# HB-UNI-Sen-TEMP-DS18B20.net
KiCad netlist of a schematic drawn in EAGLE
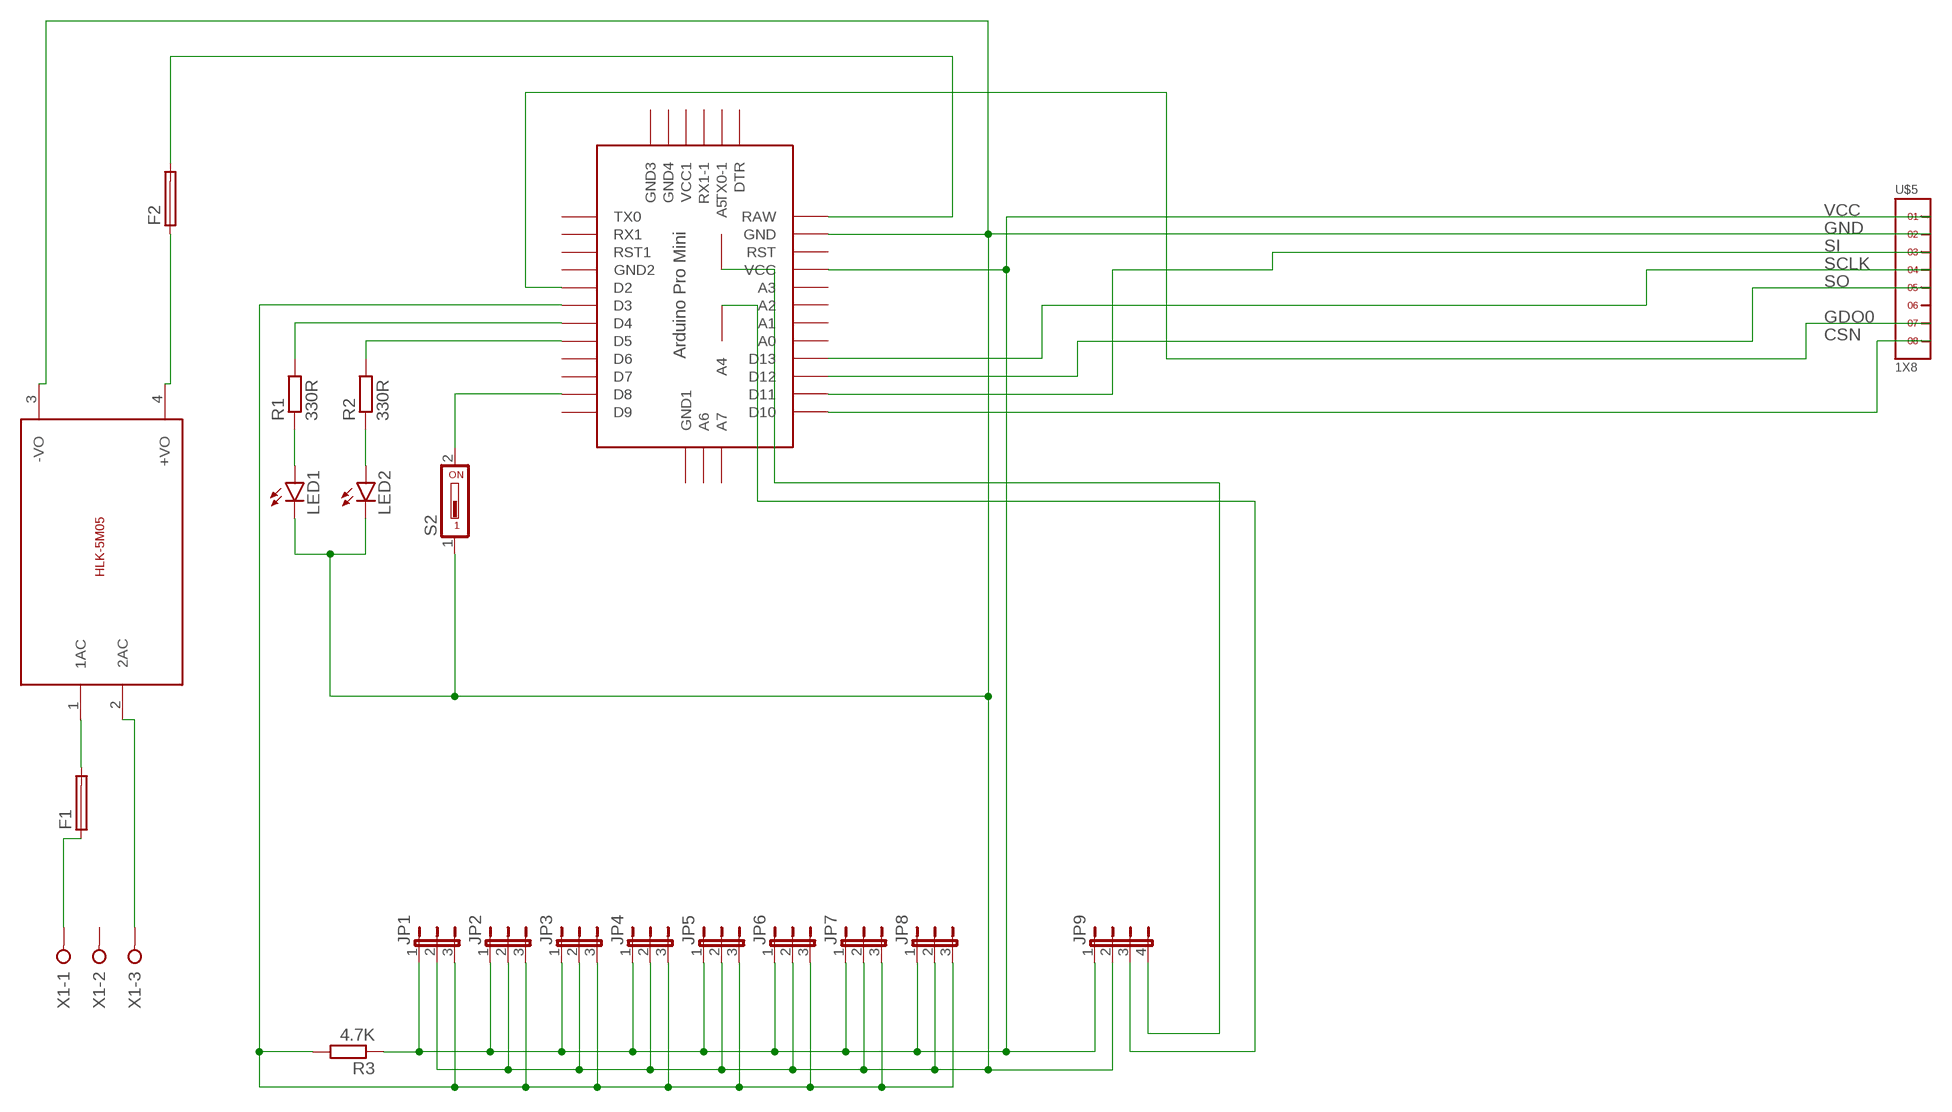
[diagram p0: schematic, sheet 1]

(export (version "E")
  (design (tool "Eeschema 10.0.6"))
  (components
    (comp (ref "F1")
      (value "GSH15")
      (footprint "eagle-import:GSH15")
      (fields (field (name "MPN") "64900001039"))
      (libsource (lib "eagle-import") (part "GSH15"))
    )
    (comp (ref "F2")
      (value "GSH15")
      (footprint "eagle-import:GSH15")
      (fields (field (name "MPN") "64900001039"))
      (libsource (lib "eagle-import") (part "GSH15"))
    )
    (comp (ref "JP1")
      (value "JP2W")
      (footprint "eagle-import:JP2W")
      (libsource (lib "eagle-import") (part "JP2W"))
    )
    (comp (ref "JP2")
      (value "JP2W")
      (footprint "eagle-import:JP2W")
      (libsource (lib "eagle-import") (part "JP2W"))
    )
    (comp (ref "JP3")
      (value "JP2W")
      (footprint "eagle-import:JP2W")
      (libsource (lib "eagle-import") (part "JP2W"))
    )
    (comp (ref "JP4")
      (value "JP2W")
      (footprint "eagle-import:JP2W")
      (libsource (lib "eagle-import") (part "JP2W"))
    )
    (comp (ref "JP5")
      (value "JP2W")
      (footprint "eagle-import:JP2W")
      (libsource (lib "eagle-import") (part "JP2W"))
    )
    (comp (ref "JP6")
      (value "JP2W")
      (footprint "eagle-import:JP2W")
      (libsource (lib "eagle-import") (part "JP2W"))
    )
    (comp (ref "JP7")
      (value "JP2W")
      (footprint "eagle-import:JP2W")
      (libsource (lib "eagle-import") (part "JP2W"))
    )
    (comp (ref "JP8")
      (value "JP2W")
      (footprint "eagle-import:JP2W")
      (libsource (lib "eagle-import") (part "JP2W"))
    )
    (comp (ref "JP9")
      (value "JP4E")
      (footprint "eagle-import:JP4")
      (libsource (lib "eagle-import") (part "JP4E"))
    )
    (comp (ref "LED1")
      (value "LED5MM")
      (footprint "eagle-import:LED5MM")
      (libsource (lib "eagle-import") (part "LED5MM"))
    )
    (comp (ref "LED2")
      (value "LED5MM")
      (footprint "eagle-import:LED5MM")
      (libsource (lib "eagle-import") (part "LED5MM"))
    )
    (comp (ref "R1")
      (value "330R")
      (footprint "eagle-import:0207_10")
      (libsource (lib "eagle-import") (part "R-EU_0207/10"))
    )
    (comp (ref "R2")
      (value "330R")
      (footprint "eagle-import:0207_10")
      (libsource (lib "eagle-import") (part "R-EU_0207/10"))
    )
    (comp (ref "R3")
      (value "4.7K")
      (footprint "eagle-import:0207_10")
      (libsource (lib "eagle-import") (part "R-EU_0207/10"))
    )
    (comp (ref "S2")
      (value "DS01")
      (footprint "eagle-import:DS-01")
      (libsource (lib "eagle-import") (part "DS01"))
    )
    (comp (ref "U$1")
      (value "ABK-PRO-MINI")
      (footprint "eagle-import:ABK-PRO-MINI")
      (libsource (lib "eagle-import") (part "ABK-PRO-MINI"))
    )
    (comp (ref "U$3")
      (value "5VDC/5W")
      (footprint "eagle-import:HLK-5M05")
      (libsource (lib "eagle-import") (part "HLK-5M05"))
    )
    (comp (ref "U$5")
      (value "1X8")
      (footprint "eagle-import:1X8")
      (libsource (lib "eagle-import") (part "1X8"))
    )
    (comp (ref "X1")
      (value "W237-3E")
      (footprint "eagle-import:W237-3E")
      (libsource (lib "eagle-import") (part "W237-3E"))
    )
  )
  (nets
    (net (code "1") (name "/CSN") (class "Default")
      (node (ref "U$1") (pin "D10") (pinfunction "D10_D10") (pintype "bidirectional"))
      (node (ref "U$5") (pin "8") (pinfunction "8_8") (pintype "bidirectional"))
    )
    (net (code "2") (name "/GDO0") (class "Default")
      (node (ref "U$1") (pin "D2") (pinfunction "D2_D2") (pintype "bidirectional"))
      (node (ref "U$5") (pin "7") (pinfunction "7_7") (pintype "bidirectional"))
    )
    (net (code "3") (name "/GND") (class "Default")
      (node (ref "JP1") (pin "2") (pinfunction "2_2") (pintype "passive"))
      (node (ref "JP2") (pin "2") (pinfunction "2_2") (pintype "passive"))
      (node (ref "JP3") (pin "2") (pinfunction "2_2") (pintype "passive"))
      (node (ref "JP4") (pin "2") (pinfunction "2_2") (pintype "passive"))
      (node (ref "JP5") (pin "2") (pinfunction "2_2") (pintype "passive"))
      (node (ref "JP6") (pin "2") (pinfunction "2_2") (pintype "passive"))
      (node (ref "JP7") (pin "2") (pinfunction "2_2") (pintype "passive"))
      (node (ref "JP8") (pin "2") (pinfunction "2_2") (pintype "passive"))
      (node (ref "JP9") (pin "2") (pinfunction "2_2") (pintype "passive"))
      (node (ref "LED1") (pin "K") (pinfunction "C_K") (pintype "passive"))
      (node (ref "LED2") (pin "K") (pinfunction "C_K") (pintype "passive"))
      (node (ref "S2") (pin "1") (pinfunction "1_1") (pintype "passive"))
      (node (ref "U$1") (pin "GND") (pinfunction "GND_GND") (pintype "bidirectional"))
      (node (ref "U$3") (pin "3") (pinfunction "-VO_3") (pintype "bidirectional"))
      (node (ref "U$5") (pin "2") (pinfunction "2_2") (pintype "bidirectional"))
    )
    (net (code "4") (name "/SCLK") (class "Default")
      (node (ref "U$1") (pin "D13") (pinfunction "D13_D13") (pintype "bidirectional"))
      (node (ref "U$5") (pin "4") (pinfunction "4_4") (pintype "bidirectional"))
    )
    (net (code "5") (name "/SI") (class "Default")
      (node (ref "U$1") (pin "D11") (pinfunction "D11_D11") (pintype "bidirectional"))
      (node (ref "U$5") (pin "3") (pinfunction "3_3") (pintype "bidirectional"))
    )
    (net (code "6") (name "/SO") (class "Default")
      (node (ref "U$1") (pin "D12") (pinfunction "D12_D12") (pintype "bidirectional"))
      (node (ref "U$5") (pin "5") (pinfunction "5_5") (pintype "bidirectional"))
    )
    (net (code "7") (name "/VCC") (class "Default")
      (node (ref "JP1") (pin "1") (pinfunction "1_1") (pintype "passive"))
      (node (ref "JP2") (pin "1") (pinfunction "1_1") (pintype "passive"))
      (node (ref "JP3") (pin "1") (pinfunction "1_1") (pintype "passive"))
      (node (ref "JP4") (pin "1") (pinfunction "1_1") (pintype "passive"))
      (node (ref "JP5") (pin "1") (pinfunction "1_1") (pintype "passive"))
      (node (ref "JP6") (pin "1") (pinfunction "1_1") (pintype "passive"))
      (node (ref "JP7") (pin "1") (pinfunction "1_1") (pintype "passive"))
      (node (ref "JP8") (pin "1") (pinfunction "1_1") (pintype "passive"))
      (node (ref "JP9") (pin "1") (pinfunction "1_1") (pintype "passive"))
      (node (ref "R3") (pin "1") (pinfunction "1_1") (pintype "passive"))
      (node (ref "U$1") (pin "VCC") (pinfunction "VCC_VCC") (pintype "bidirectional"))
      (node (ref "U$5") (pin "1") (pinfunction "1_1") (pintype "bidirectional"))
    )
    (net (code "8") (name "Net-(F2-Pad2)") (class "Default")
      (node (ref "F2") (pin "2") (pinfunction "2_2") (pintype "passive"))
      (node (ref "U$1") (pin "RAW") (pinfunction "RAW_RAW") (pintype "bidirectional"))
    )
    (net (code "9") (name "Net-(JP1-Pad3)") (class "Default")
      (node (ref "JP1") (pin "3") (pinfunction "3_3") (pintype "passive"))
      (node (ref "JP2") (pin "3") (pinfunction "3_3") (pintype "passive"))
      (node (ref "JP3") (pin "3") (pinfunction "3_3") (pintype "passive"))
      (node (ref "JP4") (pin "3") (pinfunction "3_3") (pintype "passive"))
      (node (ref "JP5") (pin "3") (pinfunction "3_3") (pintype "passive"))
      (node (ref "JP6") (pin "3") (pinfunction "3_3") (pintype "passive"))
      (node (ref "JP7") (pin "3") (pinfunction "3_3") (pintype "passive"))
      (node (ref "JP8") (pin "3") (pinfunction "3_3") (pintype "passive"))
      (node (ref "R3") (pin "2") (pinfunction "2_2") (pintype "passive"))
      (node (ref "U$1") (pin "D3") (pinfunction "D3_D3") (pintype "bidirectional"))
    )
    (net (code "10") (name "Net-(JP9-Pad3)") (class "Default")
      (node (ref "JP9") (pin "3") (pinfunction "3_3") (pintype "passive"))
      (node (ref "U$1") (pin "A4") (pinfunction "A4_A4") (pintype "bidirectional"))
    )
    (net (code "11") (name "Net-(JP9-Pad4)") (class "Default")
      (node (ref "JP9") (pin "4") (pinfunction "4_4") (pintype "passive"))
      (node (ref "U$1") (pin "A5") (pinfunction "A5_A5") (pintype "bidirectional"))
    )
    (net (code "12") (name "Net-(LED1-PadA)") (class "Default")
      (node (ref "LED1") (pin "A") (pinfunction "A_A") (pintype "passive"))
      (node (ref "R1") (pin "1") (pinfunction "1_1") (pintype "passive"))
    )
    (net (code "13") (name "Net-(LED2-PadA)") (class "Default")
      (node (ref "LED2") (pin "A") (pinfunction "A_A") (pintype "passive"))
      (node (ref "R2") (pin "1") (pinfunction "1_1") (pintype "passive"))
    )
    (net (code "14") (name "Net-(R1-Pad2)") (class "Default")
      (node (ref "R1") (pin "2") (pinfunction "2_2") (pintype "passive"))
      (node (ref "U$1") (pin "D4") (pinfunction "D4_D4") (pintype "bidirectional"))
    )
    (net (code "15") (name "Net-(R2-Pad2)") (class "Default")
      (node (ref "R2") (pin "2") (pinfunction "2_2") (pintype "passive"))
      (node (ref "U$1") (pin "D5") (pinfunction "D5_D5") (pintype "bidirectional"))
    )
    (net (code "16") (name "Net-(S2-Pad2)") (class "Default")
      (node (ref "S2") (pin "2") (pinfunction "2_2") (pintype "passive"))
      (node (ref "U$1") (pin "D8") (pinfunction "D8_D8") (pintype "bidirectional"))
    )
    (net (code "17") (name "Net-(U$3-+VO)") (class "Default")
      (node (ref "F2") (pin "1") (pinfunction "1_1") (pintype "passive"))
      (node (ref "U$3") (pin "4") (pinfunction "+VO_4") (pintype "bidirectional"))
    )
    (net (code "18") (name "Net-(U$3-1AC)") (class "Default")
      (node (ref "F1") (pin "2") (pinfunction "2_2") (pintype "passive"))
      (node (ref "U$3") (pin "1") (pinfunction "1AC_1") (pintype "bidirectional"))
    )
    (net (code "19") (name "Net-(U$3-2AC)") (class "Default")
      (node (ref "U$3") (pin "2") (pinfunction "2AC_2") (pintype "bidirectional"))
      (node (ref "X1") (pin "3") (pinfunction "KL_3") (pintype "passive"))
    )
    (net (code "20") (name "Net-(X1A-KL)") (class "Default")
      (node (ref "F1") (pin "1") (pinfunction "1_1") (pintype "passive"))
      (node (ref "X1") (pin "1") (pinfunction "KL_1") (pintype "passive"))
    )
    (net (code "21") (name "unconnected-(U$1-GND1-PadGND4)") (class "Default")
      (node (ref "U$1") (pin "GND4") (pinfunction "GND1_GND4") (pintype "bidirectional"))
    )
    (net (code "22") (name "unconnected-(U$1-GND2-PadGND1)") (class "Default")
      (node (ref "U$1") (pin "GND1") (pinfunction "GND2_GND1") (pintype "bidirectional"))
    )
    (net (code "23") (name "unconnected-(U$1-GND3-PadGND2)") (class "Default")
      (node (ref "U$1") (pin "GND2") (pinfunction "GND3_GND2") (pintype "bidirectional"))
    )
    (net (code "24") (name "unconnected-(U$1-GND4-PadGND3)") (class "Default")
      (node (ref "U$1") (pin "GND3") (pinfunction "GND4_GND3") (pintype "bidirectional"))
    )
    (net (code "25") (name "unconnected-(U$1-PadA0)") (class "Default")
      (node (ref "U$1") (pin "A0") (pinfunction "A0_A0") (pintype "bidirectional"))
    )
    (net (code "26") (name "unconnected-(U$1-PadA1)") (class "Default")
      (node (ref "U$1") (pin "A1") (pinfunction "A1_A1") (pintype "bidirectional"))
    )
    (net (code "27") (name "unconnected-(U$1-PadA2)") (class "Default")
      (node (ref "U$1") (pin "A2") (pinfunction "A2_A2") (pintype "bidirectional"))
    )
    (net (code "28") (name "unconnected-(U$1-PadA3)") (class "Default")
      (node (ref "U$1") (pin "A3") (pinfunction "A3_A3") (pintype "bidirectional"))
    )
    (net (code "29") (name "unconnected-(U$1-PadA6)") (class "Default")
      (node (ref "U$1") (pin "A6") (pinfunction "A6_A6") (pintype "bidirectional"))
    )
    (net (code "30") (name "unconnected-(U$1-PadA7)") (class "Default")
      (node (ref "U$1") (pin "A7") (pinfunction "A7_A7") (pintype "bidirectional"))
    )
    (net (code "31") (name "unconnected-(U$1-PadD6)") (class "Default")
      (node (ref "U$1") (pin "D6") (pinfunction "D6_D6") (pintype "bidirectional"))
    )
    (net (code "32") (name "unconnected-(U$1-PadD7)") (class "Default")
      (node (ref "U$1") (pin "D7") (pinfunction "D7_D7") (pintype "bidirectional"))
    )
    (net (code "33") (name "unconnected-(U$1-PadD9)") (class "Default")
      (node (ref "U$1") (pin "D9") (pinfunction "D9_D9") (pintype "bidirectional"))
    )
    (net (code "34") (name "unconnected-(U$1-PadDTR)") (class "Default")
      (node (ref "U$1") (pin "DTR") (pinfunction "DTR_DTR") (pintype "bidirectional"))
    )
    (net (code "35") (name "unconnected-(U$1-PadRST)") (class "Default")
      (node (ref "U$1") (pin "RST") (pinfunction "RST_RST") (pintype "bidirectional"))
    )
    (net (code "36") (name "unconnected-(U$1-PadRST1)") (class "Default")
      (node (ref "U$1") (pin "RST1") (pinfunction "RST1_RST1") (pintype "bidirectional"))
    )
    (net (code "37") (name "unconnected-(U$1-PadRX1)") (class "Default")
      (node (ref "U$1") (pin "RX1") (pinfunction "RX1_RX1") (pintype "bidirectional"))
    )
    (net (code "38") (name "unconnected-(U$1-PadRX1-1)") (class "Default")
      (node (ref "U$1") (pin "RX1-1") (pinfunction "RX1-1_RX1-1") (pintype "bidirectional"))
    )
    (net (code "39") (name "unconnected-(U$1-PadTX0)") (class "Default")
      (node (ref "U$1") (pin "TX0") (pinfunction "TX0_TX0") (pintype "bidirectional"))
    )
    (net (code "40") (name "unconnected-(U$1-PadTX0-1)") (class "Default")
      (node (ref "U$1") (pin "TX0-1") (pinfunction "TX0-1_TX0-1") (pintype "bidirectional"))
    )
    (net (code "41") (name "unconnected-(U$1-PadVCC1)") (class "Default")
      (node (ref "U$1") (pin "VCC1") (pinfunction "VCC1_VCC1") (pintype "bidirectional"))
    )
    (net (code "42") (name "unconnected-(U$5-Pad6)") (class "Default")
      (node (ref "U$5") (pin "6") (pinfunction "6_6") (pintype "bidirectional"))
    )
    (net (code "43") (name "unconnected-(X1B-KL-Pad2)") (class "Default")
      (node (ref "X1") (pin "2") (pinfunction "KL_2") (pintype "passive"))
    )
  )
)
